# Sheet1.net
KiCad netlist of a schematic drawn in Altium Designer
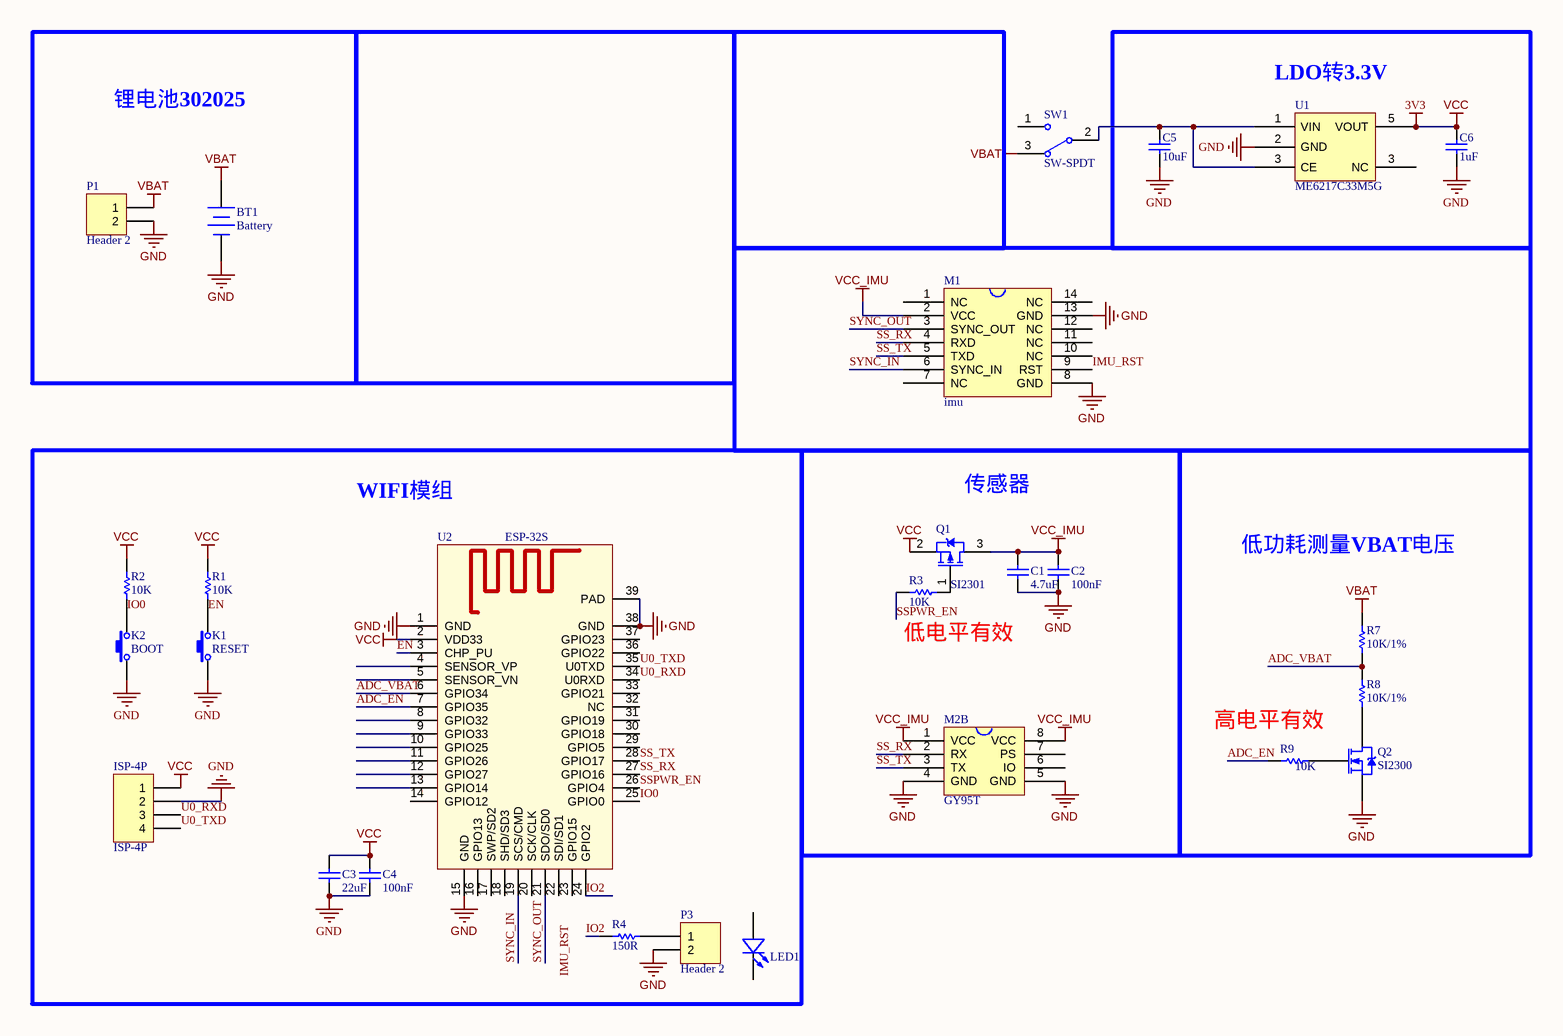
[diagram p0: Sheet1.SchDoc]

(export (version "E")
  (design (tool "Eeschema 10.0.6"))
  (components
    (comp (ref "BT1")
      (value "Battery")
      (footprint "BATTERY-302025")
      (libsource (lib "Miscellaneous") (part "Battery"))
    )
    (comp (ref "C1")
      (value "4.7uF")
      (footprint "0402C")
      (description "Capacitor")
      (fields (field (name "PUBLISHER") "Altium Limited"))
      (libsource (lib "*") (part "CAP"))
    )
    (comp (ref "C2")
      (value "100nF")
      (footprint "0402C")
      (description "Capacitor")
      (fields (field (name "PUBLISHER") "Altium Limited"))
      (libsource (lib "*") (part "CAP"))
    )
    (comp (ref "C3")
      (value "22uF")
      (footprint "0805C")
      (description "Capacitor")
      (fields (field (name "PUBLISHER") "Altium Limited"))
      (libsource (lib "*") (part "CAP"))
    )
    (comp (ref "C4")
      (value "100nF")
      (footprint "0402C")
      (description "Capacitor")
      (fields (field (name "PUBLISHER") "Altium Limited"))
      (libsource (lib "*") (part "CAP"))
    )
    (comp (ref "C5")
      (value "10uF")
      (footprint "0402C")
      (description "Capacitor")
      (libsource (lib "Discrete") (part "Cap"))
    )
    (comp (ref "C6")
      (value "1uF")
      (footprint "0402C")
      (description "Capacitor")
      (libsource (lib "Discrete") (part "Cap"))
    )
    (comp (ref "ISP-4P")
      (value "ISP-4P")
      (footprint "ISP-4P-2.0/SMD")
      (description "Header, 4-Pin")
      (fields (field (name "PUBLISHER") "Altium Limited"))
      (libsource (lib "Connector") (part "ISP-4P"))
    )
    (comp (ref "K1")
      (value "RESET")
      (footprint "KEY-SMD/2P/3*4")
      (libsource (lib "Miscellaneous") (part "BUTTON_2P"))
    )
    (comp (ref "K2")
      (value "BOOT")
      (footprint "KEY-SMD/2P/3*4")
      (libsource (lib "Miscellaneous") (part "BUTTON_2P"))
    )
    (comp (ref "LED1") (value "LED") (footprint "0603LED") (libsource (lib "Miscellaneous") (part "LED")))
    (comp (ref "M1") (value "imu") (footprint "HI229") (libsource (lib "Module") (part "HI229")))
    (comp (ref "M2") (value "GY95T") (footprint "GY95T") (libsource (lib "Module") (part "GY95T")))
    (comp (ref "P1")
      (value "Header 2")
      (footprint "CON-1.25-2P")
      (description "Header, 2-Pin")
      (fields (field (name "PUBLISHER") "Altium Limited"))
      (libsource (lib "Connector") (part "Header 2"))
    )
    (comp (ref "P3")
      (value "Header 2")
      (footprint "HDR1X2")
      (description "Header, 2-Pin")
      (fields (field (name "PUBLISHER") "Altium Limited"))
      (libsource (lib "") (part "Header 2_1"))
    )
    (comp (ref "Q1")
      (value "SI2301")
      (footprint "SOT-23")
      (description "P-Channel Power MOSFET")
      (libsource (lib "Miscellaneous") (part "MOSFET-P"))
    )
    (comp (ref "Q2")
      (value "SI2300")
      (footprint "SOT-23")
      (description "N-Channel Power MOSFET")
      (libsource (lib "Miscellaneous") (part "MOSFET-N"))
    )
    (comp (ref "R1")
      (value "10K")
      (footprint "0402")
      (description "Resistor")
      (libsource (lib "Discrete") (part "Res1"))
    )
    (comp (ref "R2")
      (value "10K")
      (footprint "0402")
      (description "Resistor")
      (libsource (lib "Discrete") (part "Res1"))
    )
    (comp (ref "R3")
      (value "10K")
      (footprint "0402")
      (description "Resistor")
      (libsource (lib "Discrete") (part "Res1"))
    )
    (comp (ref "R4")
      (value "150R")
      (footprint "0402")
      (description "Resistor")
      (libsource (lib "Discrete") (part "Res1"))
    )
    (comp (ref "R7")
      (value "10K/1%")
      (footprint "0402")
      (description "Resistor")
      (libsource (lib "Discrete") (part "Res1"))
    )
    (comp (ref "R8")
      (value "10K/1%")
      (footprint "0402")
      (description "Resistor")
      (libsource (lib "Discrete") (part "Res1"))
    )
    (comp (ref "R9")
      (value "10K")
      (footprint "0402")
      (description "Resistor")
      (libsource (lib "Discrete") (part "Res1"))
    )
    (comp (ref "SW1")
      (value "SW-SPDT")
      (footprint "SW_MSK12C01")
      (description "SPDT Subminiature Toggle Switch, Right Angle Mounting, Vertical Actuation")
      (libsource (lib "Connector") (part "SW-SPDT"))
    )
    (comp (ref "U1")
      (value "ME6217C33M5G")
      (footprint "SOT-23-5")
      (description "2~6V Input, 350mA output，Voltage LDO")
      (libsource (lib "IC") (part "ME6212"))
    )
    (comp (ref "U2")
      (value "ESP-32S")
      (footprint "ESP-32S")
      (description "ESP32-S系列模组")
      (libsource (lib "Module") (part "ESP-32S"))
    )
  )
  (nets
    (net (code "1") (name "/ADC_EN") (class "Default")
      (node (ref "R9") (pin "2") (pinfunction "2_2") (pintype "passive"))
      (node (ref "U2") (pin "7") (pinfunction "GPIO35_7") (pintype "passive"))
    )
    (net (code "2") (name "/ADC_VBAT") (class "Default")
      (node (ref "R7") (pin "1") (pinfunction "1_1") (pintype "passive"))
      (node (ref "R8") (pin "2") (pinfunction "2_2") (pintype "passive"))
      (node (ref "U2") (pin "6") (pinfunction "GPIO34_6") (pintype "passive"))
    )
    (net (code "3") (name "/EN") (class "Default")
      (node (ref "K1") (pin "2") (pinfunction "2_2") (pintype "passive"))
      (node (ref "R1") (pin "2") (pinfunction "2_2") (pintype "passive"))
      (node (ref "U2") (pin "3") (pinfunction "CHP_PU_3") (pintype "passive"))
    )
    (net (code "4") (name "/IMU_RST") (class "Default")
      (node (ref "M1") (pin "9") (pinfunction "RST_9") (pintype "passive"))
    )
    (net (code "5") (name "/IO0") (class "Default")
      (node (ref "K2") (pin "2") (pinfunction "2_2") (pintype "passive"))
      (node (ref "R2") (pin "1") (pinfunction "1_1") (pintype "passive"))
      (node (ref "U2") (pin "25") (pinfunction "GPIO0_25") (pintype "passive"))
    )
    (net (code "6") (name "/IO2") (class "Default")
      (node (ref "R4") (pin "1") (pinfunction "1_1") (pintype "passive"))
      (node (ref "U2") (pin "24") (pinfunction "GPIO2_24") (pintype "passive"))
    )
    (net (code "7") (name "/SSPWR_EN") (class "Default")
      (node (ref "R3") (pin "2") (pinfunction "2_2") (pintype "passive"))
      (node (ref "U2") (pin "26") (pinfunction "GPIO4_26") (pintype "passive"))
    )
    (net (code "8") (name "/SS_RX") (class "Default")
      (node (ref "M1") (pin "4") (pinfunction "RXD_4") (pintype "passive"))
      (node (ref "M2") (pin "2") (pinfunction "RX_2") (pintype "passive"))
      (node (ref "U2") (pin "27") (pinfunction "GPIO16_27") (pintype "passive"))
    )
    (net (code "9") (name "/SS_TX") (class "Default")
      (node (ref "M1") (pin "5") (pinfunction "TXD_5") (pintype "passive"))
      (node (ref "M2") (pin "3") (pinfunction "TX_3") (pintype "passive"))
      (node (ref "U2") (pin "28") (pinfunction "GPIO17_28") (pintype "passive"))
    )
    (net (code "10") (name "/SYNC_IN") (class "Default")
      (node (ref "M1") (pin "6") (pinfunction "SYNC_IN_6") (pintype "passive"))
      (node (ref "U2") (pin "19") (pinfunction "SCS/CMD_19") (pintype "passive"))
    )
    (net (code "11") (name "/SYNC_OUT") (class "Default")
      (node (ref "M1") (pin "3") (pinfunction "SYNC_OUT_3") (pintype "passive"))
      (node (ref "U2") (pin "21") (pinfunction "SDO/SD0_21") (pintype "passive"))
    )
    (net (code "12") (name "/U0_RXD") (class "Default")
      (node (ref "ISP-4P") (pin "3") (pinfunction "3_3") (pintype "passive"))
      (node (ref "U2") (pin "34") (pinfunction "U0RXD_34") (pintype "passive"))
    )
    (net (code "13") (name "/U0_TXD") (class "Default")
      (node (ref "ISP-4P") (pin "4") (pinfunction "4_4") (pintype "passive"))
      (node (ref "U2") (pin "35") (pinfunction "U0TXD_35") (pintype "passive"))
    )
    (net (code "14") (name "3V3") (class "Default")
      (node (ref "C3") (pin "1") (pinfunction "1_1") (pintype "passive"))
      (node (ref "C4") (pin "1") (pinfunction "1_1") (pintype "passive"))
      (node (ref "C6") (pin "2") (pinfunction "2_2") (pintype "passive"))
      (node (ref "ISP-4P") (pin "1") (pinfunction "1_1") (pintype "passive"))
      (node (ref "Q1") (pin "2") (pinfunction "S_2") (pintype "passive"))
      (node (ref "R1") (pin "1") (pinfunction "1_1") (pintype "passive"))
      (node (ref "R2") (pin "2") (pinfunction "2_2") (pintype "passive"))
      (node (ref "U1") (pin "5") (pinfunction "VOUT_5") (pintype "passive"))
      (node (ref "U2") (pin "2") (pinfunction "VDD33_2") (pintype "passive"))
    )
    (net (code "15") (name "GND") (class "Default")
      (node (ref "BT1") (pin "2") (pinfunction "-_2") (pintype "passive"))
      (node (ref "C1") (pin "2") (pinfunction "2_2") (pintype "passive"))
      (node (ref "C2") (pin "2") (pinfunction "2_2") (pintype "passive"))
      (node (ref "C3") (pin "2") (pinfunction "2_2") (pintype "passive"))
      (node (ref "C4") (pin "2") (pinfunction "2_2") (pintype "passive"))
      (node (ref "C5") (pin "1") (pinfunction "1_1") (pintype "passive"))
      (node (ref "C6") (pin "1") (pinfunction "1_1") (pintype "passive"))
      (node (ref "ISP-4P") (pin "2") (pinfunction "2_2") (pintype "passive"))
      (node (ref "K1") (pin "1") (pinfunction "1_1") (pintype "passive"))
      (node (ref "K2") (pin "1") (pinfunction "1_1") (pintype "passive"))
      (node (ref "M1") (pin "13") (pinfunction "GND_13") (pintype "passive"))
      (node (ref "M1") (pin "8") (pinfunction "GND_8") (pintype "passive"))
      (node (ref "M2") (pin "4") (pinfunction "GND_4") (pintype "passive"))
      (node (ref "M2") (pin "5") (pinfunction "GND_5") (pintype "passive"))
      (node (ref "P1") (pin "2") (pinfunction "2_2") (pintype "passive"))
      (node (ref "P3") (pin "2") (pinfunction "2_2") (pintype "passive"))
      (node (ref "Q2") (pin "2") (pinfunction "S_2") (pintype "passive"))
      (node (ref "U1") (pin "2") (pinfunction "GND_2") (pintype "passive"))
      (node (ref "U2") (pin "1") (pinfunction "GND_1") (pintype "passive"))
      (node (ref "U2") (pin "15") (pinfunction "GND_15") (pintype "passive"))
      (node (ref "U2") (pin "38") (pinfunction "GND_38") (pintype "passive"))
      (node (ref "U2") (pin "39") (pinfunction "PAD_39") (pintype "passive"))
    )
    (net (code "16") (name "Net-(P3-Pad1)") (class "Default")
      (node (ref "P3") (pin "1") (pinfunction "1_1") (pintype "passive"))
      (node (ref "R4") (pin "2") (pinfunction "2_2") (pintype "passive"))
    )
    (net (code "17") (name "Net-(Q1-G)") (class "Default")
      (node (ref "Q1") (pin "1") (pinfunction "G_1") (pintype "passive"))
      (node (ref "R3") (pin "1") (pinfunction "1_1") (pintype "passive"))
    )
    (net (code "18") (name "Net-(Q2-D)") (class "Default")
      (node (ref "Q2") (pin "3") (pinfunction "D_3") (pintype "passive"))
      (node (ref "R8") (pin "1") (pinfunction "1_1") (pintype "passive"))
    )
    (net (code "19") (name "Net-(Q2-G)") (class "Default")
      (node (ref "Q2") (pin "1") (pinfunction "G_1") (pintype "passive"))
      (node (ref "R9") (pin "1") (pinfunction "1_1") (pintype "passive"))
    )
    (net (code "20") (name "Net-(U1-CE)") (class "Default")
      (node (ref "C5") (pin "2") (pinfunction "2_2") (pintype "passive"))
      (node (ref "SW1") (pin "2") (pintype "passive"))
      (node (ref "U1") (pin "1") (pinfunction "VIN_1") (pintype "passive"))
      (node (ref "U1") (pin "3") (pinfunction "CE_3") (pintype "passive"))
    )
    (net (code "21") (name "VBAT") (class "Default")
      (node (ref "BT1") (pin "1") (pinfunction "+_1") (pintype "passive"))
      (node (ref "P1") (pin "1") (pinfunction "1_1") (pintype "passive"))
      (node (ref "R7") (pin "2") (pinfunction "2_2") (pintype "passive"))
      (node (ref "SW1") (pin "3") (pintype "passive"))
    )
    (net (code "22") (name "VCC_IMU") (class "Default")
      (node (ref "C1") (pin "1") (pinfunction "1_1") (pintype "passive"))
      (node (ref "C2") (pin "1") (pinfunction "1_1") (pintype "passive"))
      (node (ref "M1") (pin "2") (pinfunction "VCC_2") (pintype "passive"))
      (node (ref "M2") (pin "1") (pinfunction "VCC_1") (pintype "passive"))
      (node (ref "M2") (pin "8") (pinfunction "VCC_8") (pintype "passive"))
      (node (ref "Q1") (pin "3") (pinfunction "D_3") (pintype "passive"))
    )
    (net (code "23") (name "unconnected-(LED1-A-Pad1)") (class "Default")
      (node (ref "LED1") (pin "1") (pinfunction "A_1") (pintype "passive"))
    )
    (net (code "24") (name "unconnected-(LED1-K-Pad2)") (class "Default")
      (node (ref "LED1") (pin "2") (pinfunction "K_2") (pintype "passive"))
    )
    (net (code "25") (name "unconnected-(M1-NC-Pad1)") (class "Default")
      (node (ref "M1") (pin "1") (pinfunction "NC_1") (pintype "passive"))
    )
    (net (code "26") (name "unconnected-(M1-NC-Pad7)") (class "Default")
      (node (ref "M1") (pin "7") (pinfunction "NC_7") (pintype "passive"))
    )
    (net (code "27") (name "unconnected-(M1-NC-Pad10)") (class "Default")
      (node (ref "M1") (pin "10") (pinfunction "NC_10") (pintype "passive"))
    )
    (net (code "28") (name "unconnected-(M1-NC-Pad11)") (class "Default")
      (node (ref "M1") (pin "11") (pinfunction "NC_11") (pintype "passive"))
    )
    (net (code "29") (name "unconnected-(M1-NC-Pad12)") (class "Default")
      (node (ref "M1") (pin "12") (pinfunction "NC_12") (pintype "passive"))
    )
    (net (code "30") (name "unconnected-(M1-NC-Pad14)") (class "Default")
      (node (ref "M1") (pin "14") (pinfunction "NC_14") (pintype "passive"))
    )
    (net (code "31") (name "unconnected-(M2B-IO-Pad6)") (class "Default")
      (node (ref "M2") (pin "6") (pinfunction "IO_6") (pintype "passive"))
    )
    (net (code "32") (name "unconnected-(M2B-PS-Pad7)") (class "Default")
      (node (ref "M2") (pin "7") (pinfunction "PS_7") (pintype "passive"))
    )
    (net (code "33") (name "unconnected-(SW1-Pad1)") (class "Default")
      (node (ref "SW1") (pin "1") (pintype "passive"))
    )
    (net (code "34") (name "unconnected-(U1-NC-Pad3)") (class "Default")
      (node (ref "U1") (pin "3") (pinfunction "NC_3") (pintype "passive"))
    )
    (net (code "35") (name "unconnected-(U2-GPIO5-Pad29)") (class "Default")
      (node (ref "U2") (pin "29") (pinfunction "GPIO5_29") (pintype "passive"))
    )
    (net (code "36") (name "unconnected-(U2-GPIO12-Pad14)") (class "Default")
      (node (ref "U2") (pin "14") (pinfunction "GPIO12_14") (pintype "passive"))
    )
    (net (code "37") (name "unconnected-(U2-GPIO13-Pad16)") (class "Default")
      (node (ref "U2") (pin "16") (pinfunction "GPIO13_16") (pintype "passive"))
    )
    (net (code "38") (name "unconnected-(U2-GPIO14-Pad13)") (class "Default")
      (node (ref "U2") (pin "13") (pinfunction "GPIO14_13") (pintype "passive"))
    )
    (net (code "39") (name "unconnected-(U2-GPIO15-Pad23)") (class "Default")
      (node (ref "U2") (pin "23") (pinfunction "GPIO15_23") (pintype "passive"))
    )
    (net (code "40") (name "unconnected-(U2-GPIO18-Pad30)") (class "Default")
      (node (ref "U2") (pin "30") (pinfunction "GPIO18_30") (pintype "passive"))
    )
    (net (code "41") (name "unconnected-(U2-GPIO19-Pad31)") (class "Default")
      (node (ref "U2") (pin "31") (pinfunction "GPIO19_31") (pintype "passive"))
    )
    (net (code "42") (name "unconnected-(U2-GPIO21-Pad33)") (class "Default")
      (node (ref "U2") (pin "33") (pinfunction "GPIO21_33") (pintype "passive"))
    )
    (net (code "43") (name "unconnected-(U2-GPIO22-Pad36)") (class "Default")
      (node (ref "U2") (pin "36") (pinfunction "GPIO22_36") (pintype "passive"))
    )
    (net (code "44") (name "unconnected-(U2-GPIO23-Pad37)") (class "Default")
      (node (ref "U2") (pin "37") (pinfunction "GPIO23_37") (pintype "passive"))
    )
    (net (code "45") (name "unconnected-(U2-GPIO25-Pad10)") (class "Default")
      (node (ref "U2") (pin "10") (pinfunction "GPIO25_10") (pintype "passive"))
    )
    (net (code "46") (name "unconnected-(U2-GPIO26-Pad11)") (class "Default")
      (node (ref "U2") (pin "11") (pinfunction "GPIO26_11") (pintype "passive"))
    )
    (net (code "47") (name "unconnected-(U2-GPIO27-Pad12)") (class "Default")
      (node (ref "U2") (pin "12") (pinfunction "GPIO27_12") (pintype "passive"))
    )
    (net (code "48") (name "unconnected-(U2-GPIO32-Pad8)") (class "Default")
      (node (ref "U2") (pin "8") (pinfunction "GPIO32_8") (pintype "passive"))
    )
    (net (code "49") (name "unconnected-(U2-GPIO33-Pad9)") (class "Default")
      (node (ref "U2") (pin "9") (pinfunction "GPIO33_9") (pintype "passive"))
    )
    (net (code "50") (name "unconnected-(U2-NC-Pad32)") (class "Default")
      (node (ref "U2") (pin "32") (pinfunction "NC_32") (pintype "passive"))
    )
    (net (code "51") (name "unconnected-(U2-SCK{slash}CLK-Pad20)") (class "Default")
      (node (ref "U2") (pin "20") (pinfunction "SCK/CLK_20") (pintype "passive"))
    )
    (net (code "52") (name "unconnected-(U2-SDI{slash}SD1-Pad22)") (class "Default")
      (node (ref "U2") (pin "22") (pinfunction "SDI/SD1_22") (pintype "passive"))
    )
    (net (code "53") (name "unconnected-(U2-SENSOR_VN-Pad5)") (class "Default")
      (node (ref "U2") (pin "5") (pinfunction "SENSOR_VN_5") (pintype "passive"))
    )
    (net (code "54") (name "unconnected-(U2-SENSOR_VP-Pad4)") (class "Default")
      (node (ref "U2") (pin "4") (pinfunction "SENSOR_VP_4") (pintype "passive"))
    )
    (net (code "55") (name "unconnected-(U2-SHD{slash}SD3-Pad18)") (class "Default")
      (node (ref "U2") (pin "18") (pinfunction "SHD/SD3_18") (pintype "passive"))
    )
    (net (code "56") (name "unconnected-(U2-SWP{slash}SD2-Pad17)") (class "Default")
      (node (ref "U2") (pin "17") (pinfunction "SWP/SD2_17") (pintype "passive"))
    )
  )
)
